# PSU.net
KiCad netlist of a schematic drawn in Altium Designer
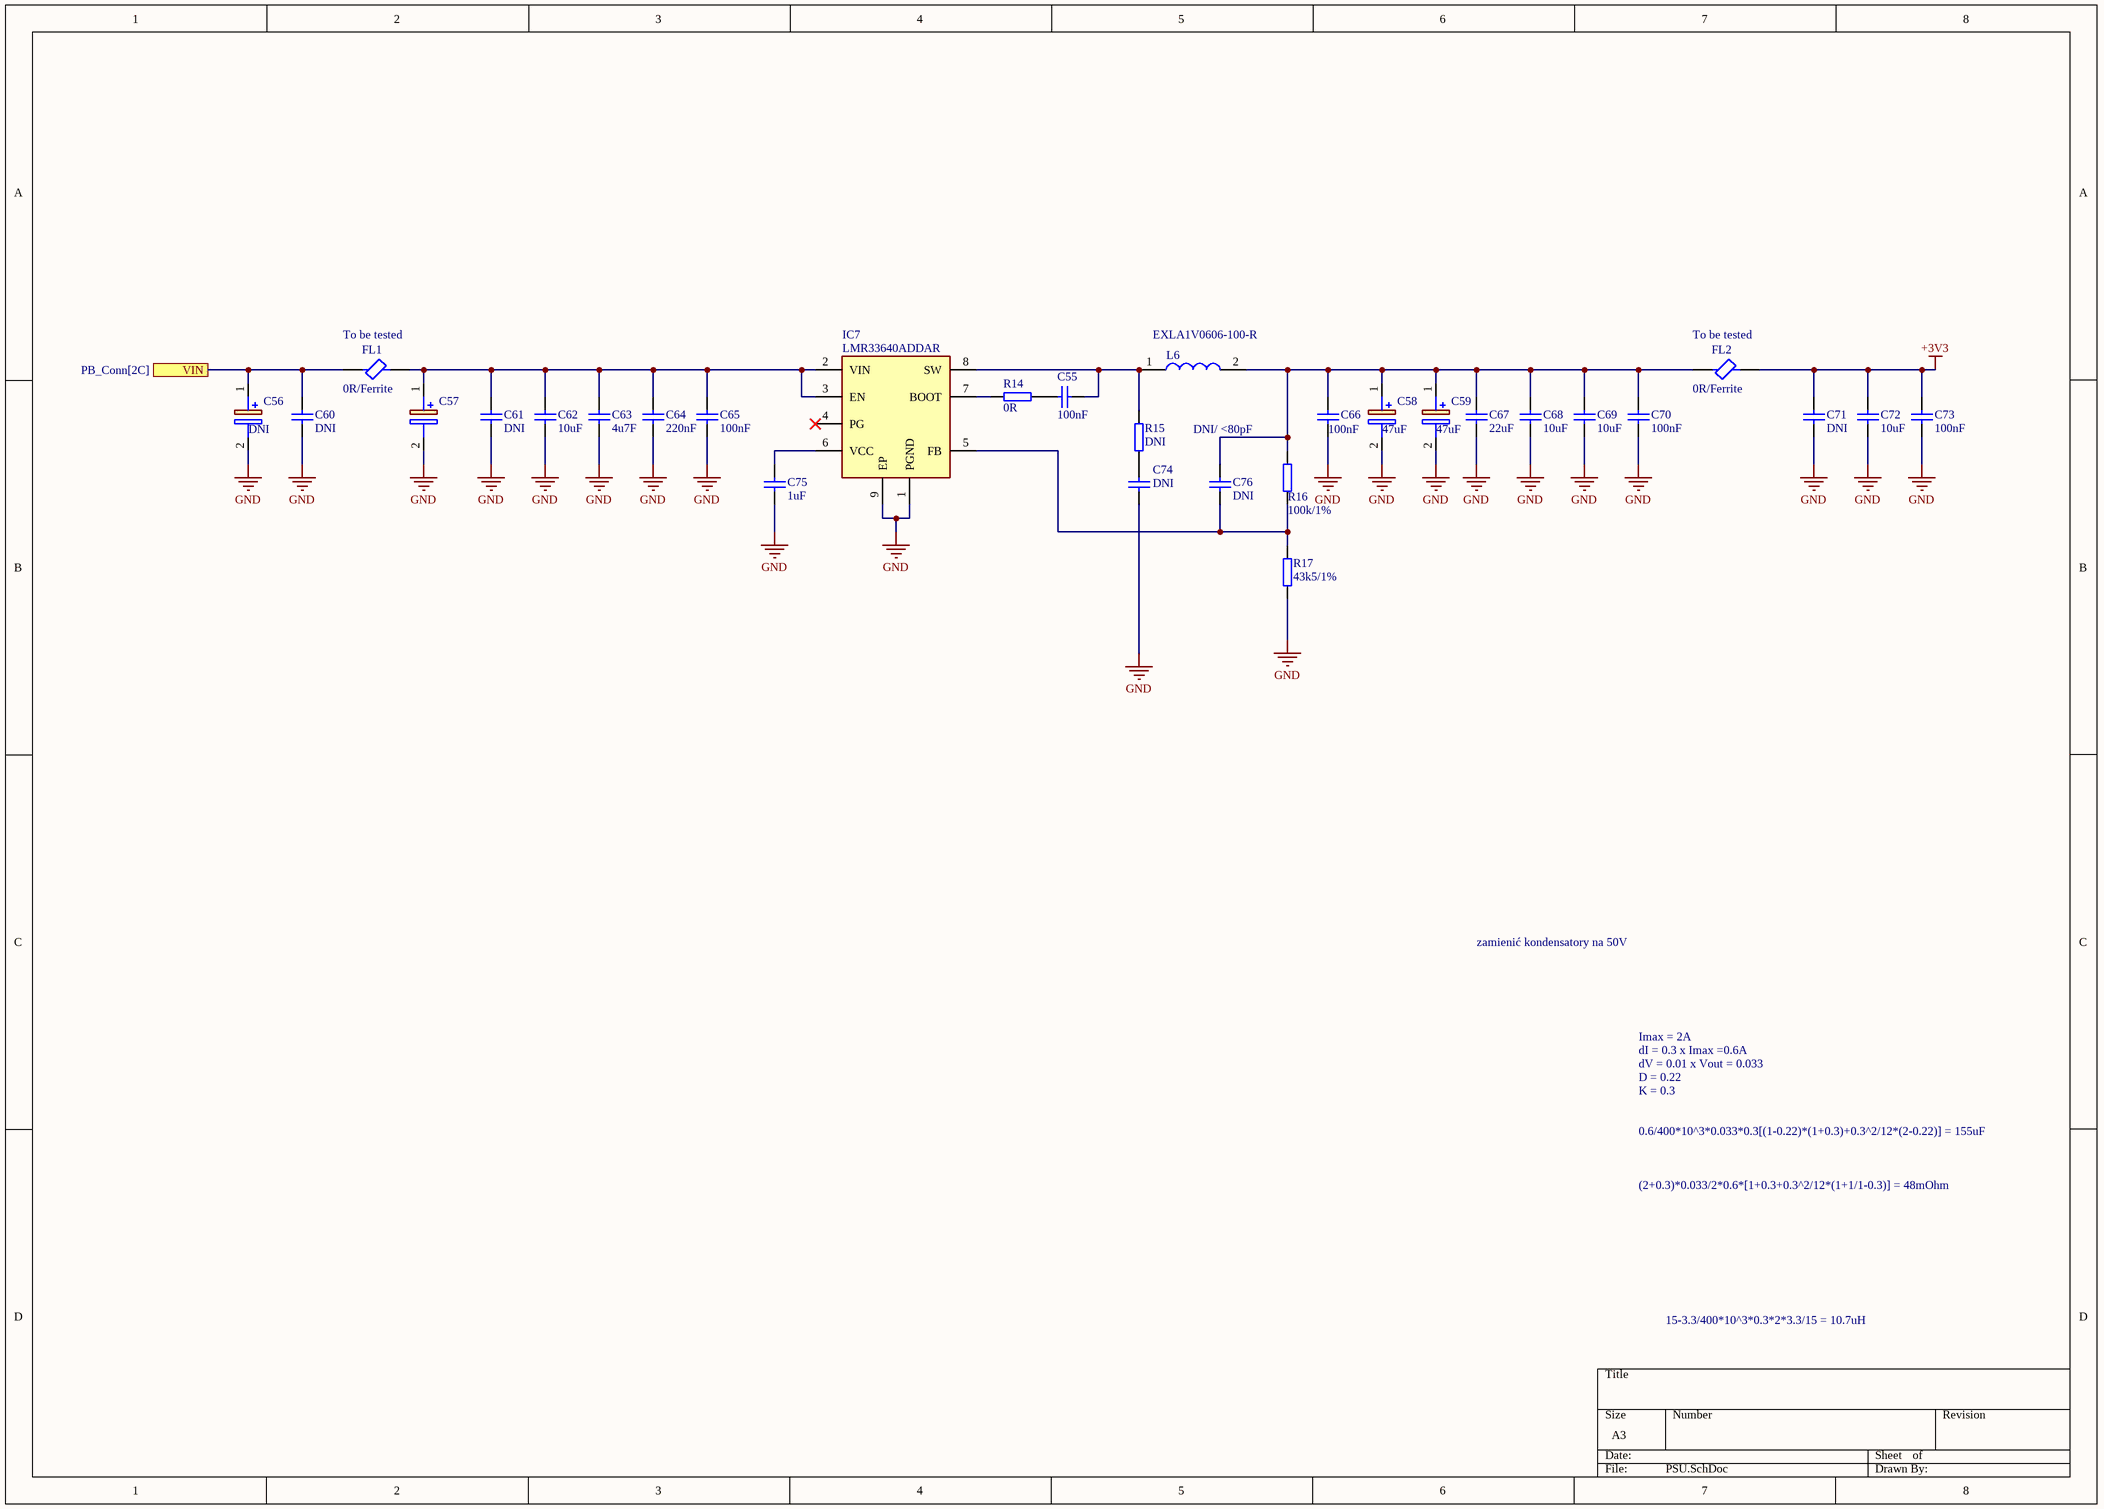
[diagram p0: PSU.SchDoc]

(export (version "E")
  (design (tool "Eeschema 10.0.6"))
  (components
    (comp (ref "C55")
      (value "100nF")
      (footprint "CAP0402")
      (fields
        (field (name "VOLTAGE") "25V")
        (field (name "MANUFACTURER_PART_NUMBER") "GRM155R71H104ME14D")
        (field (name "Comment") "Cap0402")
      )
      (libsource (lib "capacitorsSMD") (part "Cap0402"))
    )
    (comp (ref "C56")
      (value "DNI")
      (footprint "SamacSys:CAPPM7343X310N")
      (description "Capacitor Polarised")
      (fields (field (name "Comment") "TR3D336K025D0200"))
      (libsource (lib "*") (part "TR3D336K025D0200"))
    )
    (comp (ref "C57")
      (value "TR3D336K025D0200")
      (footprint "SamacSys:CAPPM7343X310N")
      (description "Capacitor Polarised")
      (fields (field (name "MOUSER PART NUMBER") "74-TR3D336K025D0200"))
      (libsource (lib "*") (part "TR3D336K025D0200"))
    )
    (comp (ref "C58")
      (value "47uF")
      (footprint "SamacSys:CAPPC2012X90N")
      (description "Capacitor Polarised")
      (fields (field (name "VOLTAGE") "6V3") (field (name "MANUFACTURER_PART_NUMBER") "T58W9476M6R3C0200"))
      (libsource (lib "*") (part "T58W9476M6R3C0200"))
    )
    (comp (ref "C59")
      (value "47uF")
      (footprint "SamacSys:CAPPC2012X90N")
      (description "Capacitor Polarised")
      (fields (field (name "VOLTAGE") "6V3") (field (name "MANUFACTURER_PART_NUMBER") "T58W9476M6R3C0200"))
      (libsource (lib "*") (part "T58W9476M6R3C0200"))
    )
    (comp (ref "C60")
      (value "DNI")
      (footprint "CAP0805")
      (fields (field (name "VOLTAGE") "35V") (field (name "Comment") "Cap0805"))
      (libsource (lib "capacitorsSMD") (part "Cap0805"))
    )
    (comp (ref "C61")
      (value "DNI")
      (footprint "CAP0805")
      (fields (field (name "VOLTAGE") "35V") (field (name "Comment") "Cap0805"))
      (libsource (lib "capacitorsSMD") (part "Cap0805"))
    )
    (comp (ref "C62")
      (value "10uF")
      (footprint "CAP0805")
      (fields
        (field (name "VOLTAGE") "35V")
        (field (name "MANUFACTURER_PART_NUMBER") "GRM21BR61H106KE43K")
        (field (name "Comment") "Cap0805")
      )
      (libsource (lib "capacitorsSMD") (part "Cap0805"))
    )
    (comp (ref "C63")
      (value "4u7F")
      (footprint "CAP0805")
      (fields
        (field (name "VOLTAGE") "35V")
        (field (name "MANUFACTURER_PART_NUMBER") "GRM21BR61H475ME51L")
        (field (name "Comment") "Cap0805")
      )
      (libsource (lib "capacitorsSMD") (part "Cap0805"))
    )
    (comp (ref "C64")
      (value "220nF")
      (footprint "CAP0402")
      (fields
        (field (name "VOLTAGE") "35V")
        (field (name "MANUFACTURER_PART_NUMBER") "GRM155R61H224ME01W")
        (field (name "Comment") "Cap0402")
      )
      (libsource (lib "capacitorsSMD") (part "Cap0402"))
    )
    (comp (ref "C65")
      (value "100nF")
      (footprint "CAP0402")
      (fields
        (field (name "VOLTAGE") "35V")
        (field (name "MANUFACTURER_PART_NUMBER") "GRM155R71H104ME14D")
        (field (name "Comment") "Cap0402")
      )
      (libsource (lib "capacitorsSMD") (part "Cap0402"))
    )
    (comp (ref "C66")
      (value "100nF")
      (footprint "CAP0402")
      (fields
        (field (name "VOLTAGE") "25V")
        (field (name "MANUFACTURER_PART_NUMBER") "GRM155R71H104ME14D")
        (field (name "Comment") "Cap0402")
      )
      (libsource (lib "capacitorsSMD") (part "Cap0402"))
    )
    (comp (ref "C67")
      (value "22uF")
      (footprint "CAP0805")
      (fields
        (field (name "VOLTAGE") "25V")
        (field (name "MANUFACTURER_PART_NUMBER") "CL21A226MAYNNNE")
        (field (name "Comment") "Cap0805")
      )
      (libsource (lib "capacitorsSMD") (part "Cap0805"))
    )
    (comp (ref "C68")
      (value "10uF")
      (footprint "CAP0603")
      (fields
        (field (name "VOLTAGE") "25V")
        (field (name "MANUFACTURER_PART_NUMBER") "GRM188R61E106MA73J")
        (field (name "Comment") "Cap0603")
      )
      (libsource (lib "capacitorsSMD") (part "Cap0603"))
    )
    (comp (ref "C69")
      (value "10uF")
      (footprint "CAP0603")
      (fields
        (field (name "VOLTAGE") "25V")
        (field (name "MANUFACTURER_PART_NUMBER") "GRM188R61E106MA73J")
        (field (name "Comment") "Cap0603")
      )
      (libsource (lib "capacitorsSMD") (part "Cap0603"))
    )
    (comp (ref "C70")
      (value "100nF")
      (footprint "CAP0402")
      (fields
        (field (name "VOLTAGE") "25V")
        (field (name "MANUFACTURER_PART_NUMBER") "GRM155R71H104ME14D")
        (field (name "Comment") "Cap0402")
      )
      (libsource (lib "capacitorsSMD") (part "Cap0402"))
    )
    (comp (ref "C71")
      (value "DNI")
      (footprint "CAP0805")
      (fields (field (name "Comment") "Cap0805"))
      (libsource (lib "capacitorsSMD") (part "Cap0805"))
    )
    (comp (ref "C72")
      (value "10uF")
      (footprint "CAP0603")
      (fields
        (field (name "VOLTAGE") "25V")
        (field (name "MANUFACTURER_PART_NUMBER") "GRM188R61E106MA73J")
        (field (name "Comment") "Cap0603")
      )
      (libsource (lib "capacitorsSMD") (part "Cap0603"))
    )
    (comp (ref "C73")
      (value "100nF")
      (footprint "CAP0402")
      (fields
        (field (name "VOLTAGE") "25V")
        (field (name "MANUFACTURER_PART_NUMBER") "GRM155R71H104ME14D")
        (field (name "Comment") "Cap0402")
      )
      (libsource (lib "capacitorsSMD") (part "Cap0402"))
    )
    (comp (ref "C74")
      (value "DNI")
      (footprint "CAP0402")
      (fields (field (name "Comment") "Cap0402"))
      (libsource (lib "capacitorsSMD") (part "Cap0402"))
    )
    (comp (ref "C75")
      (value "1uF")
      (footprint "CAP0402")
      (fields
        (field (name "VOLTAGE") "35V")
        (field (name "MANUFACTURER_PART_NUMBER") "GRM155R61H105KE05J")
        (field (name "Comment") "Cap0402")
      )
      (libsource (lib "capacitorsSMD") (part "Cap0402"))
    )
    (comp (ref "C76")
      (value "DNI")
      (footprint "CAP0402")
      (fields (field (name "Comment") "Cap0402"))
      (libsource (lib "capacitorsSMD") (part "Cap0402"))
    )
    (comp (ref "FL1")
      (value "0R/Ferrite")
      (footprint "SamacSys:BLM31KN102BH1L")
      (description "Filter")
      (libsource (lib "SamacSys") (part "BLM31KN121SH1L"))
    )
    (comp (ref "FL2")
      (value "0R/Ferrite")
      (footprint "SamacSys:BLM31KN102BH1L")
      (description "Filter")
      (libsource (lib "SamacSys") (part "BLM31KN121SH1L"))
    )
    (comp (ref "IC7")
      (value "LMR33640ADDAR")
      (footprint "SamacSys:SOIC127P600X170-9N")
      (description "Integrated Circuit")
      (libsource (lib "SamacSys") (part "LMR33640ADDAR"))
    )
    (comp (ref "L6")
      (value "EXLA1V0606-100-R")
      (footprint "SamacSys:EXLA1V0606100R")
      (description "Inductor")
      (fields (field (name "MOUSER PART NUMBER") "704-EXLA1V0606-100-R"))
      (libsource (lib "*") (part "EXLA1V0606-100-R"))
    )
    (comp (ref "R14")
      (value "0R")
      (footprint "RES0402")
      (fields (field (name "MANUFACTURER_PART_NUMBER") "RCA04020000ZSED") (field (name "Comment") "Res0402"))
      (libsource (lib "resistorSMD") (part "Res0402"))
    )
    (comp (ref "R15")
      (value "DNI")
      (footprint "RES0402")
      (fields (field (name "Comment") "Res0402"))
      (libsource (lib "resistorSMD") (part "Res0402"))
    )
    (comp (ref "R16")
      (value "100k/1%")
      (footprint "RES0402")
      (fields (field (name "MANUFACTURER_PART_NUMBER") "RC0402JR-13100KL") (field (name "Comment") "Res0402"))
      (libsource (lib "resistorSMD") (part "Res0402"))
    )
    (comp (ref "R17")
      (value "43k5/1%")
      (footprint "RES0402")
      (fields (field (name "MANUFACTURER_PART_NUMBER") "ERA-2AEB4322X") (field (name "Comment") "Res0402"))
      (libsource (lib "resistorSMD") (part "Res0402"))
    )
  )
  (nets
    (net (code "1") (name "+3V3") (class "Default")
      (node (ref "C71") (pin "2") (pinfunction "2_2") (pintype "passive"))
      (node (ref "C72") (pin "2") (pinfunction "2_2") (pintype "passive"))
      (node (ref "C73") (pin "2") (pinfunction "2_2") (pintype "passive"))
      (node (ref "FL2") (pin "2") (pinfunction "2_2") (pintype "passive"))
    )
    (net (code "2") (name "/VIN") (class "Default")
      (node (ref "C56") (pin "1") (pinfunction "+_1") (pintype "passive"))
      (node (ref "C60") (pin "2") (pinfunction "2_2") (pintype "passive"))
      (node (ref "FL1") (pin "1") (pinfunction "1_1") (pintype "passive"))
    )
    (net (code "3") (name "GND") (class "Default")
      (node (ref "C56") (pin "2") (pinfunction "-_2") (pintype "passive"))
      (node (ref "C57") (pin "2") (pinfunction "-_2") (pintype "passive"))
      (node (ref "C58") (pin "2") (pinfunction "-_2") (pintype "passive"))
      (node (ref "C59") (pin "2") (pinfunction "-_2") (pintype "passive"))
      (node (ref "C60") (pin "1") (pinfunction "1_1") (pintype "passive"))
      (node (ref "C61") (pin "1") (pinfunction "1_1") (pintype "passive"))
      (node (ref "C62") (pin "1") (pinfunction "1_1") (pintype "passive"))
      (node (ref "C63") (pin "1") (pinfunction "1_1") (pintype "passive"))
      (node (ref "C64") (pin "1") (pinfunction "1_1") (pintype "passive"))
      (node (ref "C65") (pin "1") (pinfunction "1_1") (pintype "passive"))
      (node (ref "C66") (pin "1") (pinfunction "1_1") (pintype "passive"))
      (node (ref "C67") (pin "1") (pinfunction "1_1") (pintype "passive"))
      (node (ref "C68") (pin "1") (pinfunction "1_1") (pintype "passive"))
      (node (ref "C69") (pin "1") (pinfunction "1_1") (pintype "passive"))
      (node (ref "C70") (pin "1") (pinfunction "1_1") (pintype "passive"))
      (node (ref "C71") (pin "1") (pinfunction "1_1") (pintype "passive"))
      (node (ref "C72") (pin "1") (pinfunction "1_1") (pintype "passive"))
      (node (ref "C73") (pin "1") (pinfunction "1_1") (pintype "passive"))
      (node (ref "C74") (pin "2") (pinfunction "2_2") (pintype "passive"))
      (node (ref "C75") (pin "1") (pinfunction "1_1") (pintype "passive"))
      (node (ref "IC7") (pin "1") (pinfunction "PGND_1") (pintype "passive"))
      (node (ref "IC7") (pin "9") (pinfunction "EP_9") (pintype "passive"))
      (node (ref "R17") (pin "1") (pinfunction "1_1") (pintype "passive"))
    )
    (net (code "4") (name "Net-(C55-Pad1)") (class "Default")
      (node (ref "C55") (pin "1") (pinfunction "1_1") (pintype "passive"))
      (node (ref "R14") (pin "2") (pinfunction "2_2") (pintype "passive"))
    )
    (net (code "5") (name "Net-(C57-+)") (class "Default")
      (node (ref "C57") (pin "1") (pinfunction "+_1") (pintype "passive"))
      (node (ref "C61") (pin "2") (pinfunction "2_2") (pintype "passive"))
      (node (ref "C62") (pin "2") (pinfunction "2_2") (pintype "passive"))
      (node (ref "C63") (pin "2") (pinfunction "2_2") (pintype "passive"))
      (node (ref "C64") (pin "2") (pinfunction "2_2") (pintype "passive"))
      (node (ref "C65") (pin "2") (pinfunction "2_2") (pintype "passive"))
      (node (ref "FL1") (pin "2") (pinfunction "2_2") (pintype "passive"))
      (node (ref "IC7") (pin "2") (pinfunction "VIN_2") (pintype "passive"))
      (node (ref "IC7") (pin "3") (pinfunction "EN_3") (pintype "passive"))
    )
    (net (code "6") (name "Net-(C58-+)") (class "Default")
      (node (ref "C58") (pin "1") (pinfunction "+_1") (pintype "passive"))
      (node (ref "C59") (pin "1") (pinfunction "+_1") (pintype "passive"))
      (node (ref "C66") (pin "2") (pinfunction "2_2") (pintype "passive"))
      (node (ref "C67") (pin "2") (pinfunction "2_2") (pintype "passive"))
      (node (ref "C68") (pin "2") (pinfunction "2_2") (pintype "passive"))
      (node (ref "C69") (pin "2") (pinfunction "2_2") (pintype "passive"))
      (node (ref "C70") (pin "2") (pinfunction "2_2") (pintype "passive"))
      (node (ref "C76") (pin "2") (pinfunction "2_2") (pintype "passive"))
      (node (ref "FL2") (pin "1") (pinfunction "1_1") (pintype "passive"))
      (node (ref "L6") (pin "2") (pinfunction "2_2") (pintype "passive"))
      (node (ref "R16") (pin "2") (pinfunction "2_2") (pintype "passive"))
    )
    (net (code "7") (name "Net-(C74-Pad1)") (class "Default")
      (node (ref "C74") (pin "1") (pinfunction "1_1") (pintype "passive"))
      (node (ref "R15") (pin "2") (pinfunction "2_2") (pintype "passive"))
    )
    (net (code "8") (name "Net-(IC7A-BOOT)") (class "Default")
      (node (ref "IC7") (pin "7") (pinfunction "BOOT_7") (pintype "passive"))
      (node (ref "R14") (pin "1") (pinfunction "1_1") (pintype "passive"))
    )
    (net (code "9") (name "Net-(IC7A-FB)") (class "Default")
      (node (ref "C76") (pin "1") (pinfunction "1_1") (pintype "passive"))
      (node (ref "IC7") (pin "5") (pinfunction "FB_5") (pintype "power_in"))
      (node (ref "R16") (pin "1") (pinfunction "1_1") (pintype "passive"))
      (node (ref "R17") (pin "2") (pinfunction "2_2") (pintype "passive"))
    )
    (net (code "10") (name "Net-(IC7A-SW)") (class "Default")
      (node (ref "C55") (pin "2") (pinfunction "2_2") (pintype "passive"))
      (node (ref "IC7") (pin "8") (pinfunction "SW_8") (pintype "power_in"))
      (node (ref "L6") (pin "1") (pinfunction "1_1") (pintype "passive"))
      (node (ref "R15") (pin "1") (pinfunction "1_1") (pintype "passive"))
    )
    (net (code "11") (name "Net-(IC7A-VCC)") (class "Default")
      (node (ref "C75") (pin "2") (pinfunction "2_2") (pintype "passive"))
      (node (ref "IC7") (pin "6") (pinfunction "VCC_6") (pintype "passive"))
    )
    (net (code "12") (name "unconnected-(IC7A-PG-Pad4)") (class "Default")
      (node (ref "IC7") (pin "4") (pinfunction "PG_4") (pintype "passive+no_connect"))
    )
  )
)
